# fensterkontakte.net
KiCad netlist of a schematic drawn in EAGLE
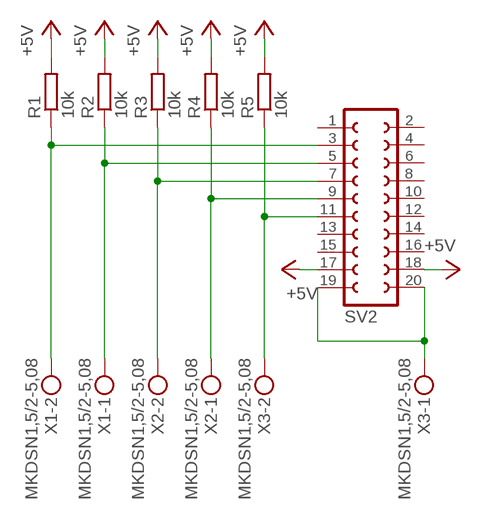
[diagram p0: schematic, sheet 1]

(export (version "E")
  (design (tool "Eeschema 10.0.6"))
  (components
    (comp (ref "R1")
      (value "10k")
      (footprint "eagle-import:M0805")
      (libsource (lib "eagle-import") (part "R-EU_M0805"))
    )
    (comp (ref "R2")
      (value "10k")
      (footprint "eagle-import:M0805")
      (libsource (lib "eagle-import") (part "R-EU_M0805"))
    )
    (comp (ref "R3")
      (value "10k")
      (footprint "eagle-import:M0805")
      (libsource (lib "eagle-import") (part "R-EU_M0805"))
    )
    (comp (ref "R4")
      (value "10k")
      (footprint "eagle-import:M0805")
      (libsource (lib "eagle-import") (part "R-EU_M0805"))
    )
    (comp (ref "R5")
      (value "10k")
      (footprint "eagle-import:M0805")
      (libsource (lib "eagle-import") (part "R-EU_M0805"))
    )
    (comp (ref "SV2")
      (value "FE10-2")
      (footprint "eagle-import:FE10-2")
      (libsource (lib "eagle-import") (part "FE10-2"))
    )
    (comp (ref "X1")
      (value "MKDSN1,5/2-5,08")
      (footprint "eagle-import:MKDSN1,5_2-5,08")
      (libsource (lib "eagle-import") (part "MKDSN1,5/2-5,08"))
    )
    (comp (ref "X2")
      (value "MKDSN1,5/2-5,08")
      (footprint "eagle-import:MKDSN1,5_2-5,08")
      (libsource (lib "eagle-import") (part "MKDSN1,5/2-5,08"))
    )
    (comp (ref "X3")
      (value "MKDSN1,5/2-5,08")
      (footprint "eagle-import:MKDSN1,5_2-5,08")
      (libsource (lib "eagle-import") (part "MKDSN1,5/2-5,08"))
    )
  )
  (nets
    (net (code "1") (name "+5V") (class "Default")
      (node (ref "R1") (pin "2") (pinfunction "2_2") (pintype "passive"))
      (node (ref "R2") (pin "2") (pinfunction "2_2") (pintype "passive"))
      (node (ref "R3") (pin "2") (pinfunction "2_2") (pintype "passive"))
      (node (ref "R4") (pin "2") (pinfunction "2_2") (pintype "passive"))
      (node (ref "R5") (pin "2") (pinfunction "2_2") (pintype "passive"))
      (node (ref "SV2") (pin "17") (pinfunction "17_17") (pintype "passive"))
      (node (ref "SV2") (pin "18") (pinfunction "18_18") (pintype "passive"))
    )
    (net (code "2") (name "Net-(X1A-KL)") (class "Default")
      (node (ref "R2") (pin "1") (pinfunction "1_1") (pintype "passive"))
      (node (ref "SV2") (pin "5") (pinfunction "5_5") (pintype "passive"))
      (node (ref "X1") (pin "1") (pinfunction "KL_1") (pintype "passive"))
    )
    (net (code "3") (name "Net-(X1B-KL)") (class "Default")
      (node (ref "R1") (pin "1") (pinfunction "1_1") (pintype "passive"))
      (node (ref "SV2") (pin "3") (pinfunction "3_3") (pintype "passive"))
      (node (ref "X1") (pin "2") (pinfunction "KL_2") (pintype "passive"))
    )
    (net (code "4") (name "Net-(X2A-KL)") (class "Default")
      (node (ref "R4") (pin "1") (pinfunction "1_1") (pintype "passive"))
      (node (ref "SV2") (pin "9") (pinfunction "9_9") (pintype "passive"))
      (node (ref "X2") (pin "1") (pinfunction "KL_1") (pintype "passive"))
    )
    (net (code "5") (name "Net-(X2B-KL)") (class "Default")
      (node (ref "R3") (pin "1") (pinfunction "1_1") (pintype "passive"))
      (node (ref "SV2") (pin "7") (pinfunction "7_7") (pintype "passive"))
      (node (ref "X2") (pin "2") (pinfunction "KL_2") (pintype "passive"))
    )
    (net (code "6") (name "Net-(X3A-KL)") (class "Default")
      (node (ref "SV2") (pin "19") (pinfunction "19_19") (pintype "passive"))
      (node (ref "SV2") (pin "20") (pinfunction "20_20") (pintype "passive"))
      (node (ref "X3") (pin "1") (pinfunction "KL_1") (pintype "passive"))
    )
    (net (code "7") (name "Net-(X3B-KL)") (class "Default")
      (node (ref "R5") (pin "1") (pinfunction "1_1") (pintype "passive"))
      (node (ref "SV2") (pin "11") (pinfunction "11_11") (pintype "passive"))
      (node (ref "X3") (pin "2") (pinfunction "KL_2") (pintype "passive"))
    )
    (net (code "8") (name "unconnected-(SV2-Pad1)") (class "Default")
      (node (ref "SV2") (pin "1") (pinfunction "1_1") (pintype "passive"))
    )
    (net (code "9") (name "unconnected-(SV2-Pad2)") (class "Default")
      (node (ref "SV2") (pin "2") (pinfunction "2_2") (pintype "passive"))
    )
    (net (code "10") (name "unconnected-(SV2-Pad4)") (class "Default")
      (node (ref "SV2") (pin "4") (pinfunction "4_4") (pintype "passive"))
    )
    (net (code "11") (name "unconnected-(SV2-Pad6)") (class "Default")
      (node (ref "SV2") (pin "6") (pinfunction "6_6") (pintype "passive"))
    )
    (net (code "12") (name "unconnected-(SV2-Pad8)") (class "Default")
      (node (ref "SV2") (pin "8") (pinfunction "8_8") (pintype "passive"))
    )
    (net (code "13") (name "unconnected-(SV2-Pad10)") (class "Default")
      (node (ref "SV2") (pin "10") (pinfunction "10_10") (pintype "passive"))
    )
    (net (code "14") (name "unconnected-(SV2-Pad12)") (class "Default")
      (node (ref "SV2") (pin "12") (pinfunction "12_12") (pintype "passive"))
    )
    (net (code "15") (name "unconnected-(SV2-Pad13)") (class "Default")
      (node (ref "SV2") (pin "13") (pinfunction "13_13") (pintype "passive"))
    )
    (net (code "16") (name "unconnected-(SV2-Pad14)") (class "Default")
      (node (ref "SV2") (pin "14") (pinfunction "14_14") (pintype "passive"))
    )
    (net (code "17") (name "unconnected-(SV2-Pad15)") (class "Default")
      (node (ref "SV2") (pin "15") (pinfunction "15_15") (pintype "passive"))
    )
    (net (code "18") (name "unconnected-(SV2-Pad16)") (class "Default")
      (node (ref "SV2") (pin "16") (pinfunction "16_16") (pintype "passive"))
    )
  )
)
